# Driver.net
KiCad netlist of a schematic drawn in Altium Designer
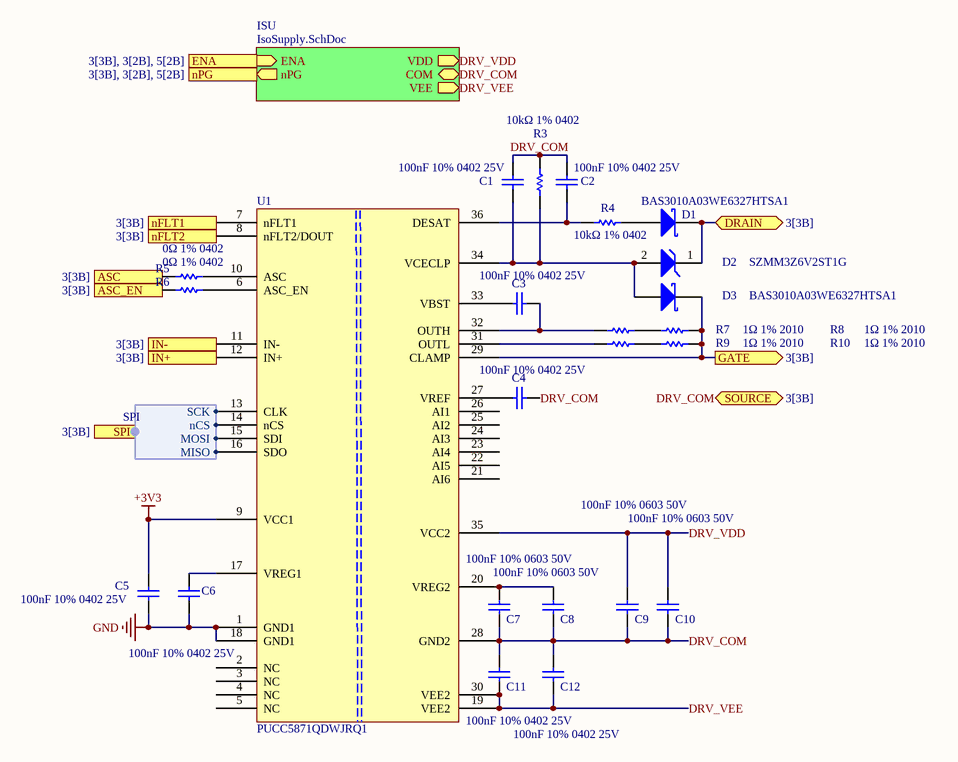
[diagram p0: Driver.SchDoc]

(export (version "E")
  (design (tool "Eeschema 10.0.6"))
  (components
    (comp (ref "C1")
      (value "100nF 10% 0402 25V")
      (footprint "0402N")
      (fields (field (name "TOLERANCE") "10") (field (name "VOLTAGE") "25"))
      (libsource (lib "MiscPassives") (part "C0402"))
    )
    (comp (ref "C2")
      (value "100nF 10% 0402 25V")
      (footprint "0402N")
      (fields (field (name "TOLERANCE") "10") (field (name "VOLTAGE") "25"))
      (libsource (lib "MiscPassives") (part "C0402"))
    )
    (comp (ref "C3")
      (value "100nF 10% 0402 25V")
      (footprint "0402N")
      (fields (field (name "TOLERANCE") "10") (field (name "VOLTAGE") "25"))
      (libsource (lib "MiscPassives") (part "C0402"))
    )
    (comp (ref "C4")
      (value "100nF 10% 0402 25V")
      (footprint "0402N")
      (fields (field (name "TOLERANCE") "10") (field (name "VOLTAGE") "25"))
      (libsource (lib "MiscPassives") (part "C0402"))
    )
    (comp (ref "C5")
      (value "100nF 10% 0402 25V")
      (footprint "0402N")
      (fields (field (name "TOLERANCE") "10") (field (name "VOLTAGE") "25"))
      (libsource (lib "MiscPassives") (part "C0402"))
    )
    (comp (ref "C6")
      (value "100nF 10% 0402 25V")
      (footprint "0402N")
      (fields (field (name "TOLERANCE") "10") (field (name "VOLTAGE") "25"))
      (libsource (lib "MiscPassives") (part "C0402"))
    )
    (comp (ref "C7")
      (value "100nF 10% 0603 50V")
      (footprint "0603N")
      (fields (field (name "TOLERANCE") "10") (field (name "VOLTAGE") "50"))
      (libsource (lib "MiscPassives") (part "C0603"))
    )
    (comp (ref "C8")
      (value "100nF 10% 0603 50V")
      (footprint "0603N")
      (fields (field (name "TOLERANCE") "10") (field (name "VOLTAGE") "50"))
      (libsource (lib "MiscPassives") (part "C0603"))
    )
    (comp (ref "C9")
      (value "100nF 10% 0603 50V")
      (footprint "0603N")
      (fields (field (name "TOLERANCE") "10") (field (name "VOLTAGE") "50"))
      (libsource (lib "MiscPassives") (part "C0603"))
    )
    (comp (ref "C10")
      (value "100nF 10% 0603 50V")
      (footprint "0603N")
      (fields (field (name "TOLERANCE") "10") (field (name "VOLTAGE") "50"))
      (libsource (lib "MiscPassives") (part "C0603"))
    )
    (comp (ref "C11")
      (value "100nF 10% 0402 25V")
      (footprint "0402N")
      (fields (field (name "TOLERANCE") "10") (field (name "VOLTAGE") "25"))
      (libsource (lib "MiscPassives") (part "C0402"))
    )
    (comp (ref "C12")
      (value "100nF 10% 0402 25V")
      (footprint "0402N")
      (fields (field (name "TOLERANCE") "10") (field (name "VOLTAGE") "25"))
      (libsource (lib "MiscPassives") (part "C0402"))
    )
    (comp (ref "D1")
      (value "BAS3010A03WE6327HTSA1")
      (footprint "INF-SOD323_V")
      (description "Medium Power AF Schottky Diode, 0.41 V, 1 A, -65 to 125 degC, 2-Pin SOD323, RoHS, Tape and Reel")
      (fields (field (name "MANUFACTURER") "Infineon"))
      (libsource (lib "Altium Content Vault") (part "DSKY-KA-2"))
    )
    (comp (ref "D2")
      (value "SZMM3Z6V2ST1G")
      (footprint "ONSC-SOD-323-2-477-02_V")
      (description "Zener Voltage Regulator, 300 mW, Tight Tolerance Portfolio, 2-Pin SOD-323, Pb-Free, Tape and Reel")
      (fields (field (name "MANUFACTURER") "On Semiconductor"))
      (libsource (lib "Altium Content Vault") (part "ONSC-K1A2-2"))
    )
    (comp (ref "D3")
      (value "BAS3010A03WE6327HTSA1")
      (footprint "INF-SOD323_V")
      (description "Medium Power AF Schottky Diode, 0.41 V, 1 A, -65 to 125 degC, 2-Pin SOD323, RoHS, Tape and Reel")
      (fields (field (name "MANUFACTURER") "Infineon"))
      (libsource (lib "Altium Content Vault") (part "DSKY-KA-2"))
    )
    (comp (ref "R3")
      (value "10kΩ 1% 0402")
      (footprint "0402N")
      (fields (field (name "TOLERANCE") "1"))
      (libsource (lib "MiscPassives") (part "R0402"))
    )
    (comp (ref "R4")
      (value "10kΩ 1% 0402")
      (footprint "0402N")
      (fields (field (name "TOLERANCE") "1"))
      (libsource (lib "MiscPassives") (part "R0402"))
    )
    (comp (ref "R5")
      (value "0Ω 1% 0402")
      (footprint "0402N")
      (fields (field (name "TOLERANCE") "1"))
      (libsource (lib "MiscPassives") (part "R0402"))
    )
    (comp (ref "R6")
      (value "0Ω 1% 0402")
      (footprint "0402N")
      (fields (field (name "TOLERANCE") "1"))
      (libsource (lib "MiscPassives") (part "R0402"))
    )
    (comp (ref "R7")
      (value "1Ω 1% 2010")
      (footprint "2010N")
      (fields (field (name "TOLERANCE") "1"))
      (libsource (lib "MiscPassives") (part "R2010"))
    )
    (comp (ref "R8")
      (value "1Ω 1% 2010")
      (footprint "2010N")
      (fields (field (name "TOLERANCE") "1"))
      (libsource (lib "MiscPassives") (part "R2010"))
    )
    (comp (ref "R9")
      (value "1Ω 1% 2010")
      (footprint "2010N")
      (fields (field (name "TOLERANCE") "1"))
      (libsource (lib "MiscPassives") (part "R2010"))
    )
    (comp (ref "R10")
      (value "1Ω 1% 2010")
      (footprint "2010N")
      (fields (field (name "TOLERANCE") "1"))
      (libsource (lib "MiscPassives") (part "R2010"))
    )
    (comp (ref "U1")
      (value "PUCC5871QDWJRQ1")
      (footprint "PUCC5871QDWJRQ1-Footprint-1")
      (libsource (lib "Saule S.A") (part "PUCC5871QDWJRQ1-Symbol-1"))
    )
  )
  (nets
    (net (code "2") (name "+3V3") (class "Default")
      (node (ref "C5") (pin "2") (pinfunction "2_2") (pintype "passive"))
      (node (ref "U1") (pin "9") (pinfunction "VCC1_9") (pintype "passive"))
    )
    (net (code "3") (name "/ASC") (class "Default")
      (node (ref "R5") (pin "1") (pinfunction "1_1") (pintype "passive"))
    )
    (net (code "4") (name "/ASC_EN") (class "Default")
      (node (ref "R6") (pin "1") (pinfunction "1_1") (pintype "passive"))
    )
    (net (code "5") (name "/DRAIN") (class "Default")
      (node (ref "D1") (pin "1") (pinfunction "K_1") (pintype "passive"))
      (node (ref "D2") (pin "1") (pinfunction "K_1") (pintype "passive"))
    )
    (net (code "6") (name "/DRV_COM") (class "Default")
      (node (ref "C1") (pin "2") (pinfunction "2_2") (pintype "passive"))
      (node (ref "C10") (pin "2") (pinfunction "2_2") (pintype "passive"))
      (node (ref "C11") (pin "1") (pinfunction "1_1") (pintype "passive"))
      (node (ref "C12") (pin "1") (pinfunction "1_1") (pintype "passive"))
      (node (ref "C2") (pin "2") (pinfunction "2_2") (pintype "passive"))
      (node (ref "C4") (pin "1") (pinfunction "1_1") (pintype "passive"))
      (node (ref "C7") (pin "2") (pinfunction "2_2") (pintype "passive"))
      (node (ref "C8") (pin "2") (pinfunction "2_2") (pintype "passive"))
      (node (ref "C9") (pin "2") (pinfunction "2_2") (pintype "passive"))
      (node (ref "R3") (pin "1") (pinfunction "1_1") (pintype "passive"))
      (node (ref "U1") (pin "28") (pinfunction "GND2_28") (pintype "passive"))
    )
    (net (code "7") (name "/DRV_VDD") (class "Default")
      (node (ref "C10") (pin "1") (pinfunction "1_1") (pintype "passive"))
      (node (ref "C9") (pin "1") (pinfunction "1_1") (pintype "passive"))
      (node (ref "U1") (pin "35") (pinfunction "VCC2_35") (pintype "passive"))
    )
    (net (code "8") (name "/DRV_VEE") (class "Default")
      (node (ref "C11") (pin "2") (pinfunction "2_2") (pintype "passive"))
      (node (ref "C12") (pin "2") (pinfunction "2_2") (pintype "passive"))
      (node (ref "U1") (pin "19") (pinfunction "VEE2_19") (pintype "passive"))
      (node (ref "U1") (pin "30") (pinfunction "VEE2_30") (pintype "passive"))
    )
    (net (code "10") (name "/GATE") (class "Default")
      (node (ref "D3") (pin "1") (pinfunction "K_1") (pintype "passive"))
      (node (ref "R10") (pin "2") (pinfunction "2_2") (pintype "passive"))
      (node (ref "R8") (pin "2") (pinfunction "2_2") (pintype "passive"))
      (node (ref "U1") (pin "29") (pinfunction "CLAMP_29") (pintype "passive"))
    )
    (net (code "11") (name "/IN+") (class "Default")
      (node (ref "U1") (pin "12") (pinfunction "IN+_12") (pintype "passive"))
    )
    (net (code "12") (name "/IN-") (class "Default")
      (node (ref "U1") (pin "11") (pinfunction "IN-_11") (pintype "passive"))
    )
    (net (code "13") (name "/MISO") (class "Default")
      (node (ref "U1") (pin "16") (pinfunction "SDO_16") (pintype "passive"))
    )
    (net (code "14") (name "/MOSI") (class "Default")
      (node (ref "U1") (pin "15") (pinfunction "SDI_15") (pintype "passive"))
    )
    (net (code "15") (name "/SCK") (class "Default")
      (node (ref "U1") (pin "13") (pinfunction "CLK_13") (pintype "passive"))
    )
    (net (code "17") (name "/nCS") (class "Default")
      (node (ref "U1") (pin "14") (pinfunction "nCS_14") (pintype "passive"))
    )
    (net (code "18") (name "/nFLT1") (class "Default")
      (node (ref "U1") (pin "7") (pinfunction "nFLT1_7") (pintype "passive"))
    )
    (net (code "19") (name "/nFLT2") (class "Default")
      (node (ref "U1") (pin "8") (pinfunction "nFLT2/DOUT_8") (pintype "passive"))
    )
    (net (code "22") (name "GND") (class "Default")
      (node (ref "C5") (pin "1") (pinfunction "1_1") (pintype "passive"))
      (node (ref "C6") (pin "1") (pinfunction "1_1") (pintype "passive"))
      (node (ref "U1") (pin "1") (pinfunction "GND1_1") (pintype "passive"))
      (node (ref "U1") (pin "18") (pinfunction "GND1_18") (pintype "passive"))
    )
    (net (code "23") (name "Net-(D1-A)") (class "Default")
      (node (ref "D1") (pin "2") (pinfunction "A_2") (pintype "passive"))
      (node (ref "R4") (pin "1") (pinfunction "1_1") (pintype "passive"))
    )
    (net (code "24") (name "Net-(D2-A)") (class "Default")
      (node (ref "C1") (pin "1") (pinfunction "1_1") (pintype "passive"))
      (node (ref "D2") (pin "2") (pinfunction "A_2") (pintype "passive"))
      (node (ref "D3") (pin "2") (pinfunction "A_2") (pintype "passive"))
      (node (ref "R3") (pin "2") (pinfunction "2_2") (pintype "passive"))
      (node (ref "U1") (pin "34") (pinfunction "VCECLP_34") (pintype "passive"))
    )
    (net (code "25") (name "Net-(R7-Pad2)") (class "Default")
      (node (ref "R7") (pin "2") (pinfunction "2_2") (pintype "passive"))
      (node (ref "R8") (pin "1") (pinfunction "1_1") (pintype "passive"))
    )
    (net (code "26") (name "Net-(R10-Pad1)") (class "Default")
      (node (ref "R10") (pin "1") (pinfunction "1_1") (pintype "passive"))
      (node (ref "R9") (pin "2") (pinfunction "2_2") (pintype "passive"))
    )
    (net (code "27") (name "Net-(U1-ASC)") (class "Default")
      (node (ref "R5") (pin "2") (pinfunction "2_2") (pintype "passive"))
      (node (ref "U1") (pin "10") (pinfunction "ASC_10") (pintype "passive"))
    )
    (net (code "28") (name "Net-(U1-ASC_EN)") (class "Default")
      (node (ref "R6") (pin "2") (pinfunction "2_2") (pintype "passive"))
      (node (ref "U1") (pin "6") (pinfunction "ASC_EN_6") (pintype "passive"))
    )
    (net (code "29") (name "Net-(U1-DESAT)") (class "Default")
      (node (ref "C2") (pin "1") (pinfunction "1_1") (pintype "passive"))
      (node (ref "R4") (pin "2") (pinfunction "2_2") (pintype "passive"))
      (node (ref "U1") (pin "36") (pinfunction "DESAT_36") (pintype "passive"))
    )
    (net (code "30") (name "Net-(U1-OUTH)") (class "Default")
      (node (ref "C3") (pin "1") (pinfunction "1_1") (pintype "passive"))
      (node (ref "R7") (pin "1") (pinfunction "1_1") (pintype "passive"))
      (node (ref "U1") (pin "32") (pinfunction "OUTH_32") (pintype "passive"))
    )
    (net (code "31") (name "Net-(U1-OUTL)") (class "Default")
      (node (ref "R9") (pin "1") (pinfunction "1_1") (pintype "passive"))
      (node (ref "U1") (pin "31") (pinfunction "OUTL_31") (pintype "passive"))
    )
    (net (code "32") (name "Net-(U1-VBST)") (class "Default")
      (node (ref "C3") (pin "2") (pinfunction "2_2") (pintype "passive"))
      (node (ref "U1") (pin "33") (pinfunction "VBST_33") (pintype "passive"))
    )
    (net (code "33") (name "Net-(U1-VREF)") (class "Default")
      (node (ref "C4") (pin "2") (pinfunction "2_2") (pintype "passive"))
      (node (ref "U1") (pin "27") (pinfunction "VREF_27") (pintype "passive"))
    )
    (net (code "34") (name "Net-(U1-VREG1)") (class "Default")
      (node (ref "C6") (pin "2") (pinfunction "2_2") (pintype "passive"))
      (node (ref "U1") (pin "17") (pinfunction "VREG1_17") (pintype "passive"))
    )
    (net (code "35") (name "Net-(U1-VREG2)") (class "Default")
      (node (ref "C7") (pin "1") (pinfunction "1_1") (pintype "passive"))
      (node (ref "C8") (pin "1") (pinfunction "1_1") (pintype "passive"))
      (node (ref "U1") (pin "20") (pinfunction "VREG2_20") (pintype "passive"))
    )
    (net (code "36") (name "unconnected-(U1-AI1-Pad26)") (class "Default")
      (node (ref "U1") (pin "26") (pinfunction "AI1_26") (pintype "passive"))
    )
    (net (code "37") (name "unconnected-(U1-AI2-Pad25)") (class "Default")
      (node (ref "U1") (pin "25") (pinfunction "AI2_25") (pintype "passive"))
    )
    (net (code "38") (name "unconnected-(U1-AI3-Pad24)") (class "Default")
      (node (ref "U1") (pin "24") (pinfunction "AI3_24") (pintype "passive"))
    )
    (net (code "39") (name "unconnected-(U1-AI4-Pad23)") (class "Default")
      (node (ref "U1") (pin "23") (pinfunction "AI4_23") (pintype "passive"))
    )
    (net (code "40") (name "unconnected-(U1-AI5-Pad22)") (class "Default")
      (node (ref "U1") (pin "22") (pinfunction "AI5_22") (pintype "passive"))
    )
    (net (code "41") (name "unconnected-(U1-AI6-Pad21)") (class "Default")
      (node (ref "U1") (pin "21") (pinfunction "AI6_21") (pintype "passive"))
    )
    (net (code "42") (name "unconnected-(U1-NC-Pad2)") (class "Default")
      (node (ref "U1") (pin "2") (pinfunction "NC_2") (pintype "passive"))
    )
    (net (code "43") (name "unconnected-(U1-NC-Pad3)") (class "Default")
      (node (ref "U1") (pin "3") (pinfunction "NC_3") (pintype "passive"))
    )
    (net (code "44") (name "unconnected-(U1-NC-Pad4)") (class "Default")
      (node (ref "U1") (pin "4") (pinfunction "NC_4") (pintype "passive"))
    )
    (net (code "45") (name "unconnected-(U1-NC-Pad5)") (class "Default")
      (node (ref "U1") (pin "5") (pinfunction "NC_5") (pintype "passive"))
    )
  )
)
